# Arduino.net
KiCad netlist of a schematic drawn in EAGLE
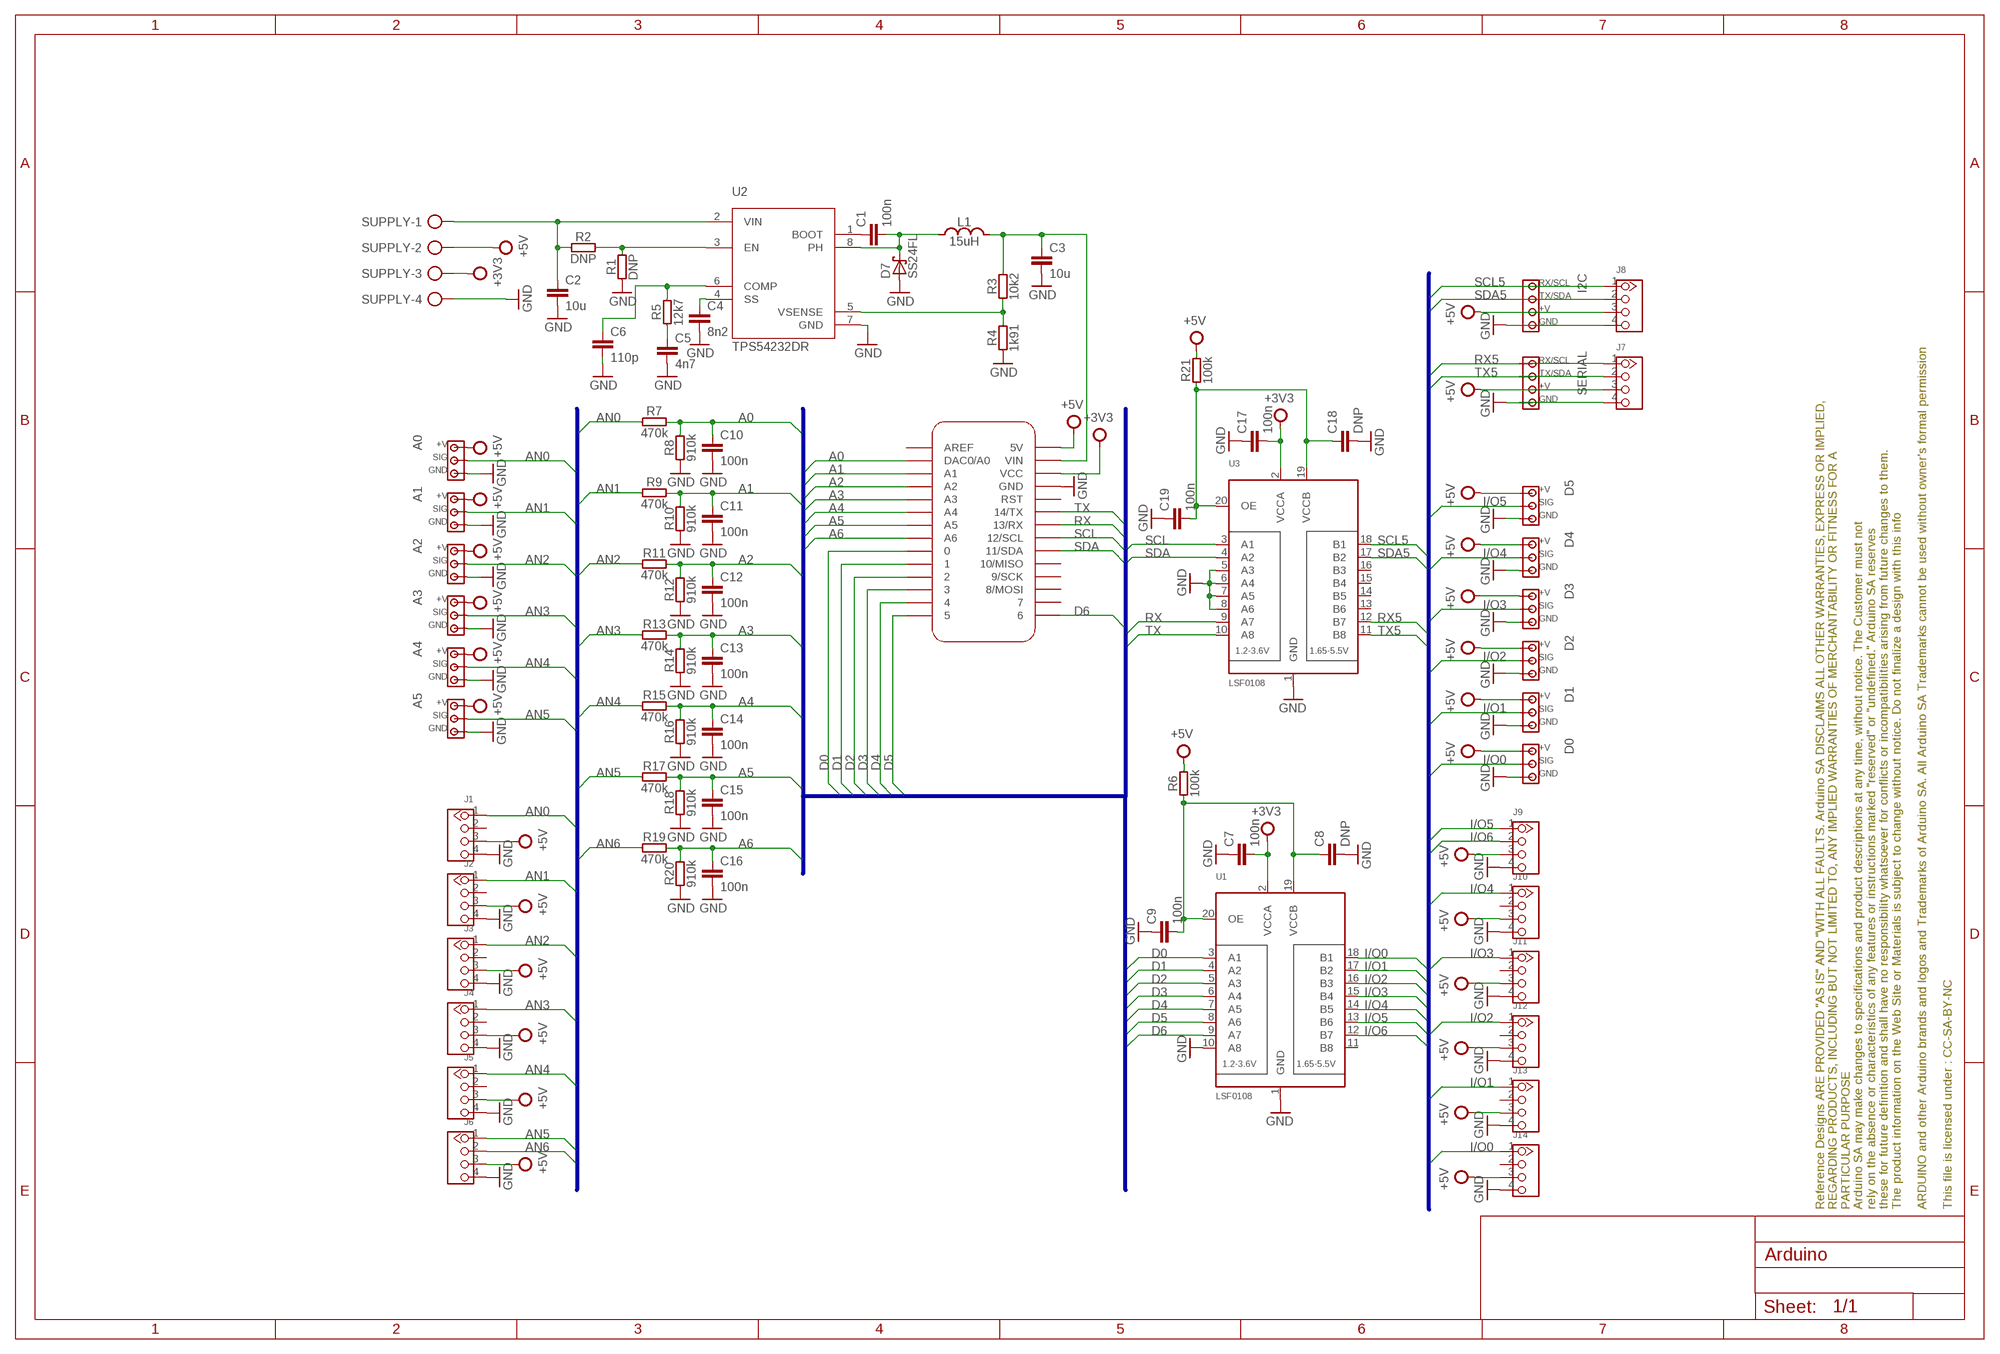
[diagram p0: schematic, sheet 1]

(export (version "E")
  (design (tool "Eeschema 10.0.6"))
  (components
    (comp (ref "A0")
      (value "DNP")
      (footprint "eagle-import:MODULINO-3SM")
      (libsource (lib "eagle-import") (part "MODULINO-3SM-DNP"))
    )
    (comp (ref "A1")
      (value "DNP")
      (footprint "eagle-import:MODULINO-3SM")
      (libsource (lib "eagle-import") (part "MODULINO-3SM-DNP"))
    )
    (comp (ref "A2")
      (value "DNP")
      (footprint "eagle-import:MODULINO-3SM")
      (libsource (lib "eagle-import") (part "MODULINO-3SM-DNP"))
    )
    (comp (ref "A3")
      (value "DNP")
      (footprint "eagle-import:MODULINO-3SM")
      (libsource (lib "eagle-import") (part "MODULINO-3SM-DNP"))
    )
    (comp (ref "A4")
      (value "DNP")
      (footprint "eagle-import:MODULINO-3SM")
      (libsource (lib "eagle-import") (part "MODULINO-3SM-DNP"))
    )
    (comp (ref "A5")
      (value "DNP")
      (footprint "eagle-import:MODULINO-3SM")
      (libsource (lib "eagle-import") (part "MODULINO-3SM-DNP"))
    )
    (comp (ref "B1")
      (value "DNP")
      (footprint "eagle-import:MKRBOARD-NOOUTLINE")
      (libsource (lib "eagle-import") (part "MKRBOARDNO-OUTLINE"))
    )
    (comp (ref "C1")
      (value "100n")
      (footprint "eagle-import:0402-1005X55N")
      (fields (field (name "MANUFACTURER") "TDK"))
      (libsource (lib "eagle-import") (part "C-0402-100NF"))
    )
    (comp (ref "C2")
      (value "10u")
      (footprint "eagle-import:0603-1608X90N")
      (fields (field (name "MANUFACTURER") "Murata"))
      (libsource (lib "eagle-import") (part "C-0603-10UF"))
    )
    (comp (ref "C3")
      (value "10u")
      (footprint "eagle-import:0603-1608X90N")
      (fields (field (name "MANUFACTURER") "Murata"))
      (libsource (lib "eagle-import") (part "C-0603-10UF"))
    )
    (comp (ref "C4")
      (value "8n2")
      (footprint "eagle-import:0402-1005X55N")
      (fields (field (name "MANUFACTURER") "Yageo"))
      (libsource (lib "eagle-import") (part "C-0402-8N2"))
    )
    (comp (ref "C5")
      (value "4n7")
      (footprint "eagle-import:0402-1005X55N")
      (fields (field (name "MANUFACTURER") "Murata"))
      (libsource (lib "eagle-import") (part "C-0402-4N7"))
    )
    (comp (ref "C6")
      (value "110p")
      (footprint "eagle-import:0402-1005X55N")
      (fields (field (name "MANUFACTURER") "Murata"))
      (libsource (lib "eagle-import") (part "C-0402-110P"))
    )
    (comp (ref "C7")
      (value "100n")
      (footprint "eagle-import:0402-1005X55N")
      (fields (field (name "MANUFACTURER") "TDK"))
      (libsource (lib "eagle-import") (part "C-0402-100NF"))
    )
    (comp (ref "C8")
      (value "DNP")
      (footprint "eagle-import:0402-1005X55N")
      (libsource (lib "eagle-import") (part "C-0402DNP"))
    )
    (comp (ref "C9")
      (value "100n")
      (footprint "eagle-import:0402-1005X55N")
      (fields (field (name "MANUFACTURER") "TDK"))
      (libsource (lib "eagle-import") (part "C-0402-100NF"))
    )
    (comp (ref "C10")
      (value "100n")
      (footprint "eagle-import:0402-1005X55N")
      (fields (field (name "MANUFACTURER") "TDK"))
      (libsource (lib "eagle-import") (part "C-0402-100NF"))
    )
    (comp (ref "C11")
      (value "100n")
      (footprint "eagle-import:0402-1005X55N")
      (fields (field (name "MANUFACTURER") "TDK"))
      (libsource (lib "eagle-import") (part "C-0402-100NF"))
    )
    (comp (ref "C12")
      (value "100n")
      (footprint "eagle-import:0402-1005X55N")
      (fields (field (name "MANUFACTURER") "TDK"))
      (libsource (lib "eagle-import") (part "C-0402-100NF"))
    )
    (comp (ref "C13")
      (value "100n")
      (footprint "eagle-import:0402-1005X55N")
      (fields (field (name "MANUFACTURER") "TDK"))
      (libsource (lib "eagle-import") (part "C-0402-100NF"))
    )
    (comp (ref "C14")
      (value "100n")
      (footprint "eagle-import:0402-1005X55N")
      (fields (field (name "MANUFACTURER") "TDK"))
      (libsource (lib "eagle-import") (part "C-0402-100NF"))
    )
    (comp (ref "C15")
      (value "100n")
      (footprint "eagle-import:0402-1005X55N")
      (fields (field (name "MANUFACTURER") "TDK"))
      (libsource (lib "eagle-import") (part "C-0402-100NF"))
    )
    (comp (ref "C16")
      (value "100n")
      (footprint "eagle-import:0402-1005X55N")
      (fields (field (name "MANUFACTURER") "TDK"))
      (libsource (lib "eagle-import") (part "C-0402-100NF"))
    )
    (comp (ref "C17")
      (value "100n")
      (footprint "eagle-import:0402-1005X55N")
      (fields (field (name "MANUFACTURER") "TDK"))
      (libsource (lib "eagle-import") (part "C-0402-100NF"))
    )
    (comp (ref "C18")
      (value "DNP")
      (footprint "eagle-import:0402-1005X55N")
      (libsource (lib "eagle-import") (part "C-0402DNP"))
    )
    (comp (ref "C19")
      (value "100n")
      (footprint "eagle-import:0402-1005X55N")
      (fields (field (name "MANUFACTURER") "TDK"))
      (libsource (lib "eagle-import") (part "C-0402-100NF"))
    )
    (comp (ref "D0")
      (value "DNP")
      (footprint "eagle-import:MODULINO-3SM")
      (libsource (lib "eagle-import") (part "MODULINO-3SM-DNP"))
    )
    (comp (ref "D1")
      (value "DNP")
      (footprint "eagle-import:MODULINO-3SM")
      (libsource (lib "eagle-import") (part "MODULINO-3SM-DNP"))
    )
    (comp (ref "D2")
      (value "DNP")
      (footprint "eagle-import:MODULINO-3SM")
      (libsource (lib "eagle-import") (part "MODULINO-3SM-DNP"))
    )
    (comp (ref "D3")
      (value "DNP")
      (footprint "eagle-import:MODULINO-3SM")
      (libsource (lib "eagle-import") (part "MODULINO-3SM-DNP"))
    )
    (comp (ref "D4")
      (value "DNP")
      (footprint "eagle-import:MODULINO-3SM")
      (libsource (lib "eagle-import") (part "MODULINO-3SM-DNP"))
    )
    (comp (ref "D5")
      (value "DNP")
      (footprint "eagle-import:MODULINO-3SM")
      (libsource (lib "eagle-import") (part "MODULINO-3SM-DNP"))
    )
    (comp (ref "D7")
      (value "SS24FL")
      (footprint "eagle-import:SOD123F")
      (fields (field (name "MANUFACTURER") "Fairchild"))
      (libsource (lib "eagle-import") (part "SS24FL"))
    )
    (comp (ref "FRAME1")
      (value "DNP")
      (footprint "eagle-import:FRAME")
      (libsource (lib "eagle-import") (part "A3-FRAME-STANDARD"))
    )
    (comp (ref "I2C")
      (value "DNP")
      (footprint "eagle-import:MODULINO-4SM")
      (libsource (lib "eagle-import") (part "MODULINO-4SM-DNP"))
    )
    (comp (ref "J1")
      (value "-")
      (footprint "eagle-import:HW4-2.0")
      (fields (field (name "MANUFACTURER") "JST"))
      (libsource (lib "eagle-import") (part "GROVE-CONNECTOR"))
    )
    (comp (ref "J2")
      (value "-")
      (footprint "eagle-import:HW4-2.0")
      (fields (field (name "MANUFACTURER") "JST"))
      (libsource (lib "eagle-import") (part "GROVE-CONNECTOR"))
    )
    (comp (ref "J3")
      (value "-")
      (footprint "eagle-import:HW4-2.0")
      (fields (field (name "MANUFACTURER") "JST"))
      (libsource (lib "eagle-import") (part "GROVE-CONNECTOR"))
    )
    (comp (ref "J4")
      (value "-")
      (footprint "eagle-import:HW4-2.0")
      (fields (field (name "MANUFACTURER") "JST"))
      (libsource (lib "eagle-import") (part "GROVE-CONNECTOR"))
    )
    (comp (ref "J5")
      (value "-")
      (footprint "eagle-import:HW4-2.0")
      (fields (field (name "MANUFACTURER") "JST"))
      (libsource (lib "eagle-import") (part "GROVE-CONNECTOR"))
    )
    (comp (ref "J6")
      (value "-")
      (footprint "eagle-import:HW4-2.0")
      (fields (field (name "MANUFACTURER") "JST"))
      (libsource (lib "eagle-import") (part "GROVE-CONNECTOR"))
    )
    (comp (ref "J7")
      (value "-")
      (footprint "eagle-import:HW4-2.0")
      (fields (field (name "MANUFACTURER") "JST"))
      (libsource (lib "eagle-import") (part "GROVE-CONNECTOR"))
    )
    (comp (ref "J8")
      (value "-")
      (footprint "eagle-import:HW4-2.0")
      (fields (field (name "MANUFACTURER") "JST"))
      (libsource (lib "eagle-import") (part "GROVE-CONNECTOR"))
    )
    (comp (ref "J9")
      (value "-")
      (footprint "eagle-import:HW4-2.0")
      (fields (field (name "MANUFACTURER") "JST"))
      (libsource (lib "eagle-import") (part "GROVE-CONNECTOR"))
    )
    (comp (ref "J10")
      (value "-")
      (footprint "eagle-import:HW4-2.0")
      (fields (field (name "MANUFACTURER") "JST"))
      (libsource (lib "eagle-import") (part "GROVE-CONNECTOR"))
    )
    (comp (ref "J11")
      (value "-")
      (footprint "eagle-import:HW4-2.0")
      (fields (field (name "MANUFACTURER") "JST"))
      (libsource (lib "eagle-import") (part "GROVE-CONNECTOR"))
    )
    (comp (ref "J12")
      (value "-")
      (footprint "eagle-import:HW4-2.0")
      (fields (field (name "MANUFACTURER") "JST"))
      (libsource (lib "eagle-import") (part "GROVE-CONNECTOR"))
    )
    (comp (ref "J13")
      (value "-")
      (footprint "eagle-import:HW4-2.0")
      (fields (field (name "MANUFACTURER") "JST"))
      (libsource (lib "eagle-import") (part "GROVE-CONNECTOR"))
    )
    (comp (ref "J14")
      (value "-")
      (footprint "eagle-import:HW4-2.0")
      (fields (field (name "MANUFACTURER") "JST"))
      (libsource (lib "eagle-import") (part "GROVE-CONNECTOR"))
    )
    (comp (ref "L1")
      (value "15uH")
      (footprint "eagle-import:SRN6045")
      (fields (field (name "MANUFACTURER") "Bourns"))
      (libsource (lib "eagle-import") (part "LSRN"))
    )
    (comp (ref "R1")
      (value "DNP")
      (footprint "eagle-import:0402-1005X55N")
      (libsource (lib "eagle-import") (part "R-0402-DNP"))
    )
    (comp (ref "R2")
      (value "DNP")
      (footprint "eagle-import:0402-1005X55N")
      (libsource (lib "eagle-import") (part "R-0402-DNP"))
    )
    (comp (ref "R3")
      (value "10k2")
      (footprint "eagle-import:0402-1005X55N")
      (fields (field (name "MANUFACTURER") "Yageo"))
      (libsource (lib "eagle-import") (part "R-0402-10K2"))
    )
    (comp (ref "R4")
      (value "1k91")
      (footprint "eagle-import:0402-1005X55N")
      (fields (field (name "MANUFACTURER") "Yageo"))
      (libsource (lib "eagle-import") (part "R-0402-1K91"))
    )
    (comp (ref "R5")
      (value "12k7")
      (footprint "eagle-import:0402-1005X55N")
      (fields (field (name "MANUFACTURER") "Yageo"))
      (libsource (lib "eagle-import") (part "R-0402-12K7"))
    )
    (comp (ref "R6")
      (value "100k")
      (footprint "eagle-import:0402-1005X55N")
      (fields (field (name "MANUFACTURER") "Yageo "))
      (libsource (lib "eagle-import") (part "R-0402-100K"))
    )
    (comp (ref "R7")
      (value "470k")
      (footprint "eagle-import:0402-1005X55N")
      (fields (field (name "MANUFACTURER") "Yageo"))
      (libsource (lib "eagle-import") (part "R-0402-470K"))
    )
    (comp (ref "R8")
      (value "910k")
      (footprint "eagle-import:0402-1005X55N")
      (fields (field (name "MANUFACTURER") "Yageo"))
      (libsource (lib "eagle-import") (part "R-0402-910K"))
    )
    (comp (ref "R9")
      (value "470k")
      (footprint "eagle-import:0402-1005X55N")
      (fields (field (name "MANUFACTURER") "Yageo"))
      (libsource (lib "eagle-import") (part "R-0402-470K"))
    )
    (comp (ref "R10")
      (value "910k")
      (footprint "eagle-import:0402-1005X55N")
      (fields (field (name "MANUFACTURER") "Yageo"))
      (libsource (lib "eagle-import") (part "R-0402-910K"))
    )
    (comp (ref "R11")
      (value "470k")
      (footprint "eagle-import:0402-1005X55N")
      (fields (field (name "MANUFACTURER") "Yageo"))
      (libsource (lib "eagle-import") (part "R-0402-470K"))
    )
    (comp (ref "R12")
      (value "910k")
      (footprint "eagle-import:0402-1005X55N")
      (fields (field (name "MANUFACTURER") "Yageo"))
      (libsource (lib "eagle-import") (part "R-0402-910K"))
    )
    (comp (ref "R13")
      (value "470k")
      (footprint "eagle-import:0402-1005X55N")
      (fields (field (name "MANUFACTURER") "Yageo"))
      (libsource (lib "eagle-import") (part "R-0402-470K"))
    )
    (comp (ref "R14")
      (value "910k")
      (footprint "eagle-import:0402-1005X55N")
      (fields (field (name "MANUFACTURER") "Yageo"))
      (libsource (lib "eagle-import") (part "R-0402-910K"))
    )
    (comp (ref "R15")
      (value "470k")
      (footprint "eagle-import:0402-1005X55N")
      (fields (field (name "MANUFACTURER") "Yageo"))
      (libsource (lib "eagle-import") (part "R-0402-470K"))
    )
    (comp (ref "R16")
      (value "910k")
      (footprint "eagle-import:0402-1005X55N")
      (fields (field (name "MANUFACTURER") "Yageo"))
      (libsource (lib "eagle-import") (part "R-0402-910K"))
    )
    (comp (ref "R17")
      (value "470k")
      (footprint "eagle-import:0402-1005X55N")
      (fields (field (name "MANUFACTURER") "Yageo"))
      (libsource (lib "eagle-import") (part "R-0402-470K"))
    )
    (comp (ref "R18")
      (value "910k")
      (footprint "eagle-import:0402-1005X55N")
      (fields (field (name "MANUFACTURER") "Yageo"))
      (libsource (lib "eagle-import") (part "R-0402-910K"))
    )
    (comp (ref "R19")
      (value "470k")
      (footprint "eagle-import:0402-1005X55N")
      (fields (field (name "MANUFACTURER") "Yageo"))
      (libsource (lib "eagle-import") (part "R-0402-470K"))
    )
    (comp (ref "R20")
      (value "910k")
      (footprint "eagle-import:0402-1005X55N")
      (fields (field (name "MANUFACTURER") "Yageo"))
      (libsource (lib "eagle-import") (part "R-0402-910K"))
    )
    (comp (ref "R21")
      (value "100k")
      (footprint "eagle-import:0402-1005X55N")
      (fields (field (name "MANUFACTURER") "Yageo "))
      (libsource (lib "eagle-import") (part "R-0402-100K"))
    )
    (comp (ref "SERIAL")
      (value "DNP")
      (footprint "eagle-import:MODULINO-4SM")
      (libsource (lib "eagle-import") (part "MODULINO-4SM-DNP"))
    )
    (comp (ref "SUPPLY")
      (value "-")
      (footprint "eagle-import:AK300_4")
      (fields (field (name "MANUFACTURER") "On Shore"))
      (libsource (lib "eagle-import") (part "AK300/4"))
    )
    (comp (ref "U1")
      (value "LSF0108")
      (footprint "eagle-import:TSSOP20")
      (fields (field (name "MANUFACTURER") "Texas Instruments "))
      (libsource (lib "eagle-import") (part "LSF0108PWR"))
    )
    (comp (ref "U2")
      (value "TPS54232DR")
      (footprint "eagle-import:SO08")
      (fields (field (name "MANUFACTURER") "Texas Instruments"))
      (libsource (lib "eagle-import") (part "TPS54232"))
    )
    (comp (ref "U3")
      (value "LSF0108")
      (footprint "eagle-import:TSSOP20")
      (fields (field (name "MANUFACTURER") "Texas Instruments "))
      (libsource (lib "eagle-import") (part "LSF0108PWR"))
    )
  )
  (nets
    (net (code "1") (name "+3V3") (class "Default")
      (node (ref "B1") (pin "VCC") (pinfunction "VCC_VCC") (pintype "bidirectional"))
      (node (ref "C17") (pin "2") (pinfunction "2_2") (pintype "passive"))
      (node (ref "C7") (pin "2") (pinfunction "2_2") (pintype "passive"))
      (node (ref "SUPPLY") (pin "3") (pinfunction "KL_3") (pintype "passive"))
      (node (ref "U1") (pin "2") (pinfunction "VCCA_2") (pintype "bidirectional"))
      (node (ref "U3") (pin "2") (pinfunction "VCCA_2") (pintype "bidirectional"))
    )
    (net (code "2") (name "+5V") (class "Default")
      (node (ref "A0") (pin "1") (pinfunction "1_1") (pintype "passive"))
      (node (ref "A1") (pin "1") (pinfunction "1_1") (pintype "passive"))
      (node (ref "A2") (pin "1") (pinfunction "1_1") (pintype "passive"))
      (node (ref "A3") (pin "1") (pinfunction "1_1") (pintype "passive"))
      (node (ref "A4") (pin "1") (pinfunction "1_1") (pintype "passive"))
      (node (ref "A5") (pin "1") (pinfunction "1_1") (pintype "passive"))
      (node (ref "B1") (pin "5V") (pinfunction "5V_5V") (pintype "bidirectional"))
      (node (ref "D0") (pin "1") (pinfunction "1_1") (pintype "passive"))
      (node (ref "D1") (pin "1") (pinfunction "1_1") (pintype "passive"))
      (node (ref "D2") (pin "1") (pinfunction "1_1") (pintype "passive"))
      (node (ref "D3") (pin "1") (pinfunction "1_1") (pintype "passive"))
      (node (ref "D4") (pin "1") (pinfunction "1_1") (pintype "passive"))
      (node (ref "D5") (pin "1") (pinfunction "1_1") (pintype "passive"))
      (node (ref "I2C") (pin "3") (pinfunction "3_3") (pintype "passive"))
      (node (ref "J1") (pin "3") (pinfunction "3_3") (pintype "bidirectional"))
      (node (ref "J10") (pin "3") (pinfunction "3_3") (pintype "bidirectional"))
      (node (ref "J11") (pin "3") (pinfunction "3_3") (pintype "bidirectional"))
      (node (ref "J12") (pin "3") (pinfunction "3_3") (pintype "bidirectional"))
      (node (ref "J13") (pin "3") (pinfunction "3_3") (pintype "bidirectional"))
      (node (ref "J14") (pin "3") (pinfunction "3_3") (pintype "bidirectional"))
      (node (ref "J2") (pin "3") (pinfunction "3_3") (pintype "bidirectional"))
      (node (ref "J3") (pin "3") (pinfunction "3_3") (pintype "bidirectional"))
      (node (ref "J4") (pin "3") (pinfunction "3_3") (pintype "bidirectional"))
      (node (ref "J5") (pin "3") (pinfunction "3_3") (pintype "bidirectional"))
      (node (ref "J6") (pin "3") (pinfunction "3_3") (pintype "bidirectional"))
      (node (ref "J7") (pin "3") (pinfunction "3_3") (pintype "bidirectional"))
      (node (ref "J8") (pin "3") (pinfunction "3_3") (pintype "bidirectional"))
      (node (ref "J9") (pin "3") (pinfunction "3_3") (pintype "bidirectional"))
      (node (ref "R21") (pin "2") (pinfunction "2_2") (pintype "passive"))
      (node (ref "R6") (pin "2") (pinfunction "2_2") (pintype "passive"))
      (node (ref "SERIAL") (pin "3") (pinfunction "3_3") (pintype "passive"))
      (node (ref "SUPPLY") (pin "2") (pinfunction "KL_2") (pintype "passive"))
    )
    (net (code "3") (name "/A0") (class "Default")
      (node (ref "B1") (pin "A0") (pinfunction "DAC0/A0_A0") (pintype "bidirectional"))
      (node (ref "C10") (pin "1") (pinfunction "1_1") (pintype "passive"))
      (node (ref "R7") (pin "2") (pinfunction "2_2") (pintype "passive"))
      (node (ref "R8") (pin "2") (pinfunction "2_2") (pintype "passive"))
    )
    (net (code "4") (name "/A1") (class "Default")
      (node (ref "B1") (pin "A1") (pinfunction "A1_A1") (pintype "bidirectional"))
      (node (ref "C11") (pin "1") (pinfunction "1_1") (pintype "passive"))
      (node (ref "R10") (pin "2") (pinfunction "2_2") (pintype "passive"))
      (node (ref "R9") (pin "2") (pinfunction "2_2") (pintype "passive"))
    )
    (net (code "5") (name "/A2") (class "Default")
      (node (ref "B1") (pin "A2") (pinfunction "A2_A2") (pintype "bidirectional"))
      (node (ref "C12") (pin "1") (pinfunction "1_1") (pintype "passive"))
      (node (ref "R11") (pin "2") (pinfunction "2_2") (pintype "passive"))
      (node (ref "R12") (pin "2") (pinfunction "2_2") (pintype "passive"))
    )
    (net (code "6") (name "/A3") (class "Default")
      (node (ref "B1") (pin "A3") (pinfunction "A3_A3") (pintype "bidirectional"))
      (node (ref "C13") (pin "1") (pinfunction "1_1") (pintype "passive"))
      (node (ref "R13") (pin "2") (pinfunction "2_2") (pintype "passive"))
      (node (ref "R14") (pin "2") (pinfunction "2_2") (pintype "passive"))
    )
    (net (code "7") (name "/A4") (class "Default")
      (node (ref "B1") (pin "A4") (pinfunction "A4_A4") (pintype "bidirectional"))
      (node (ref "C14") (pin "1") (pinfunction "1_1") (pintype "passive"))
      (node (ref "R15") (pin "2") (pinfunction "2_2") (pintype "passive"))
      (node (ref "R16") (pin "2") (pinfunction "2_2") (pintype "passive"))
    )
    (net (code "8") (name "/A5") (class "Default")
      (node (ref "B1") (pin "A5") (pinfunction "A5_A5") (pintype "bidirectional"))
      (node (ref "C15") (pin "1") (pinfunction "1_1") (pintype "passive"))
      (node (ref "R17") (pin "2") (pinfunction "2_2") (pintype "passive"))
      (node (ref "R18") (pin "2") (pinfunction "2_2") (pintype "passive"))
    )
    (net (code "9") (name "/A6") (class "Default")
      (node (ref "B1") (pin "A6") (pinfunction "A6_A6") (pintype "bidirectional"))
      (node (ref "C16") (pin "1") (pinfunction "1_1") (pintype "passive"))
      (node (ref "R19") (pin "2") (pinfunction "2_2") (pintype "passive"))
      (node (ref "R20") (pin "2") (pinfunction "2_2") (pintype "passive"))
    )
    (net (code "10") (name "/AN0") (class "Default")
      (node (ref "A0") (pin "2") (pinfunction "2_2") (pintype "passive"))
      (node (ref "J1") (pin "1") (pinfunction "1_1") (pintype "bidirectional"))
      (node (ref "R7") (pin "1") (pinfunction "1_1") (pintype "passive"))
    )
    (net (code "11") (name "/AN1") (class "Default")
      (node (ref "A1") (pin "2") (pinfunction "2_2") (pintype "passive"))
      (node (ref "J2") (pin "1") (pinfunction "1_1") (pintype "bidirectional"))
      (node (ref "R9") (pin "1") (pinfunction "1_1") (pintype "passive"))
    )
    (net (code "12") (name "/AN2") (class "Default")
      (node (ref "A2") (pin "2") (pinfunction "2_2") (pintype "passive"))
      (node (ref "J3") (pin "1") (pinfunction "1_1") (pintype "bidirectional"))
      (node (ref "R11") (pin "1") (pinfunction "1_1") (pintype "passive"))
    )
    (net (code "13") (name "/AN3") (class "Default")
      (node (ref "A3") (pin "2") (pinfunction "2_2") (pintype "passive"))
      (node (ref "J4") (pin "1") (pinfunction "1_1") (pintype "bidirectional"))
      (node (ref "R13") (pin "1") (pinfunction "1_1") (pintype "passive"))
    )
    (net (code "14") (name "/AN4") (class "Default")
      (node (ref "A4") (pin "2") (pinfunction "2_2") (pintype "passive"))
      (node (ref "J5") (pin "1") (pinfunction "1_1") (pintype "bidirectional"))
      (node (ref "R15") (pin "1") (pinfunction "1_1") (pintype "passive"))
    )
    (net (code "15") (name "/AN5") (class "Default")
      (node (ref "A5") (pin "2") (pinfunction "2_2") (pintype "passive"))
      (node (ref "J6") (pin "1") (pinfunction "1_1") (pintype "bidirectional"))
      (node (ref "R17") (pin "1") (pinfunction "1_1") (pintype "passive"))
    )
    (net (code "16") (name "/AN6") (class "Default")
      (node (ref "J6") (pin "2") (pinfunction "2_2") (pintype "bidirectional"))
      (node (ref "R19") (pin "1") (pinfunction "1_1") (pintype "passive"))
    )
    (net (code "17") (name "/D0") (class "Default")
      (node (ref "B1") (pin "0") (pinfunction "0_0") (pintype "bidirectional"))
      (node (ref "U1") (pin "3") (pinfunction "A1_3") (pintype "bidirectional"))
    )
    (net (code "18") (name "/D1") (class "Default")
      (node (ref "B1") (pin "1") (pinfunction "1_1") (pintype "bidirectional"))
      (node (ref "U1") (pin "4") (pinfunction "A2_4") (pintype "bidirectional"))
    )
    (net (code "19") (name "/D2") (class "Default")
      (node (ref "B1") (pin "2") (pinfunction "2_2") (pintype "bidirectional"))
      (node (ref "U1") (pin "5") (pinfunction "A3_5") (pintype "bidirectional"))
    )
    (net (code "20") (name "/D3") (class "Default")
      (node (ref "B1") (pin "3") (pinfunction "3_3") (pintype "bidirectional"))
      (node (ref "U1") (pin "6") (pinfunction "A4_6") (pintype "bidirectional"))
    )
    (net (code "21") (name "/D4") (class "Default")
      (node (ref "B1") (pin "4") (pinfunction "4_4") (pintype "bidirectional"))
      (node (ref "U1") (pin "7") (pinfunction "A5_7") (pintype "bidirectional"))
    )
    (net (code "22") (name "/D5") (class "Default")
      (node (ref "B1") (pin "5") (pinfunction "5_5") (pintype "bidirectional"))
      (node (ref "U1") (pin "8") (pinfunction "A6_8") (pintype "bidirectional"))
    )
    (net (code "23") (name "/D6") (class "Default")
      (node (ref "B1") (pin "6") (pinfunction "6_6") (pintype "bidirectional"))
      (node (ref "U1") (pin "9") (pinfunction "A7_9") (pintype "bidirectional"))
    )
    (net (code "24") (name "/I{slash}O0") (class "Default")
      (node (ref "D0") (pin "2") (pinfunction "2_2") (pintype "passive"))
      (node (ref "J14") (pin "1") (pinfunction "1_1") (pintype "bidirectional"))
      (node (ref "U1") (pin "18") (pinfunction "B1_18") (pintype "bidirectional"))
    )
    (net (code "25") (name "/I{slash}O1") (class "Default")
      (node (ref "D1") (pin "2") (pinfunction "2_2") (pintype "passive"))
      (node (ref "J13") (pin "1") (pinfunction "1_1") (pintype "bidirectional"))
      (node (ref "U1") (pin "17") (pinfunction "B2_17") (pintype "bidirectional"))
    )
    (net (code "26") (name "/I{slash}O2") (class "Default")
      (node (ref "D2") (pin "2") (pinfunction "2_2") (pintype "passive"))
      (node (ref "J12") (pin "1") (pinfunction "1_1") (pintype "bidirectional"))
      (node (ref "U1") (pin "16") (pinfunction "B3_16") (pintype "bidirectional"))
    )
    (net (code "27") (name "/I{slash}O3") (class "Default")
      (node (ref "D3") (pin "2") (pinfunction "2_2") (pintype "passive"))
      (node (ref "J11") (pin "1") (pinfunction "1_1") (pintype "bidirectional"))
      (node (ref "U1") (pin "15") (pinfunction "B4_15") (pintype "bidirectional"))
    )
    (net (code "28") (name "/I{slash}O4") (class "Default")
      (node (ref "D4") (pin "2") (pinfunction "2_2") (pintype "passive"))
      (node (ref "J10") (pin "1") (pinfunction "1_1") (pintype "bidirectional"))
      (node (ref "U1") (pin "14") (pinfunction "B5_14") (pintype "bidirectional"))
    )
    (net (code "29") (name "/I{slash}O5") (class "Default")
      (node (ref "D5") (pin "2") (pinfunction "2_2") (pintype "passive"))
      (node (ref "J9") (pin "1") (pinfunction "1_1") (pintype "bidirectional"))
      (node (ref "U1") (pin "13") (pinfunction "B6_13") (pintype "bidirectional"))
    )
    (net (code "30") (name "/I{slash}O6") (class "Default")
      (node (ref "J9") (pin "2") (pinfunction "2_2") (pintype "bidirectional"))
      (node (ref "U1") (pin "12") (pinfunction "B7_12") (pintype "bidirectional"))
    )
    (net (code "31") (name "/RX") (class "Default")
      (node (ref "B1") (pin "13") (pinfunction "13/RX_13") (pintype "bidirectional"))
      (node (ref "U3") (pin "9") (pinfunction "A7_9") (pintype "bidirectional"))
    )
    (net (code "32") (name "/RX5") (class "Default")
      (node (ref "J7") (pin "1") (pinfunction "1_1") (pintype "bidirectional"))
      (node (ref "SERIAL") (pin "1") (pinfunction "1_1") (pintype "passive"))
      (node (ref "U3") (pin "12") (pinfunction "B7_12") (pintype "bidirectional"))
    )
    (net (code "33") (name "/SCL") (class "Default")
      (node (ref "B1") (pin "12") (pinfunction "12/SCL_12") (pintype "bidirectional"))
      (node (ref "U3") (pin "3") (pinfunction "A1_3") (pintype "bidirectional"))
    )
    (net (code "34") (name "/SCL5") (class "Default")
      (node (ref "I2C") (pin "1") (pinfunction "1_1") (pintype "passive"))
      (node (ref "J8") (pin "1") (pinfunction "1_1") (pintype "bidirectional"))
      (node (ref "U3") (pin "18") (pinfunction "B1_18") (pintype "bidirectional"))
    )
    (net (code "35") (name "/SDA") (class "Default")
      (node (ref "B1") (pin "11") (pinfunction "11/SDA_11") (pintype "bidirectional"))
      (node (ref "U3") (pin "4") (pinfunction "A2_4") (pintype "bidirectional"))
    )
    (net (code "36") (name "/SDA5") (class "Default")
      (node (ref "I2C") (pin "2") (pinfunction "2_2") (pintype "passive"))
      (node (ref "J8") (pin "2") (pinfunction "2_2") (pintype "bidirectional"))
      (node (ref "U3") (pin "17") (pinfunction "B2_17") (pintype "bidirectional"))
    )
    (net (code "37") (name "/TX") (class "Default")
      (node (ref "B1") (pin "14") (pinfunction "14/TX_14") (pintype "bidirectional"))
      (node (ref "U3") (pin "10") (pinfunction "A8_10") (pintype "bidirectional"))
    )
    (net (code "38") (name "/TX5") (class "Default")
      (node (ref "J7") (pin "2") (pinfunction "2_2") (pintype "bidirectional"))
      (node (ref "SERIAL") (pin "2") (pinfunction "2_2") (pintype "passive"))
      (node (ref "U3") (pin "11") (pinfunction "B8_11") (pintype "bidirectional"))
    )
    (net (code "39") (name "GND") (class "Default")
      (node (ref "A0") (pin "3") (pinfunction "3_3") (pintype "passive"))
      (node (ref "A1") (pin "3") (pinfunction "3_3") (pintype "passive"))
      (node (ref "A2") (pin "3") (pinfunction "3_3") (pintype "passive"))
      (node (ref "A3") (pin "3") (pinfunction "3_3") (pintype "passive"))
      (node (ref "A4") (pin "3") (pinfunction "3_3") (pintype "passive"))
      (node (ref "A5") (pin "3") (pinfunction "3_3") (pintype "passive"))
      (node (ref "B1") (pin "GND") (pinfunction "GND_GND") (pintype "bidirectional"))
      (node (ref "C10") (pin "2") (pinfunction "2_2") (pintype "passive"))
      (node (ref "C11") (pin "2") (pinfunction "2_2") (pintype "passive"))
      (node (ref "C12") (pin "2") (pinfunction "2_2") (pintype "passive"))
      (node (ref "C13") (pin "2") (pinfunction "2_2") (pintype "passive"))
      (node (ref "C14") (pin "2") (pinfunction "2_2") (pintype "passive"))
      (node (ref "C15") (pin "2") (pinfunction "2_2") (pintype "passive"))
      (node (ref "C16") (pin "2") (pinfunction "2_2") (pintype "passive"))
      (node (ref "C17") (pin "1") (pinfunction "1_1") (pintype "passive"))
      (node (ref "C18") (pin "2") (pinfunction "2_2") (pintype "passive"))
      (node (ref "C19") (pin "1") (pinfunction "1_1") (pintype "passive"))
      (node (ref "C2") (pin "2") (pinfunction "2_2") (pintype "passive"))
      (node (ref "C3") (pin "2") (pinfunction "2_2") (pintype "passive"))
      (node (ref "C4") (pin "2") (pinfunction "2_2") (pintype "passive"))
      (node (ref "C5") (pin "2") (pinfunction "2_2") (pintype "passive"))
      (node (ref "C6") (pin "2") (pinfunction "2_2") (pintype "passive"))
      (node (ref "C7") (pin "1") (pinfunction "1_1") (pintype "passive"))
      (node (ref "C8") (pin "2") (pinfunction "2_2") (pintype "passive"))
      (node (ref "C9") (pin "1") (pinfunction "1_1") (pintype "passive"))
      (node (ref "D0") (pin "3") (pinfunction "3_3") (pintype "passive"))
      (node (ref "D1") (pin "3") (pinfunction "3_3") (pintype "passive"))
      (node (ref "D2") (pin "3") (pinfunction "3_3") (pintype "passive"))
      (node (ref "D3") (pin "3") (pinfunction "3_3") (pintype "passive"))
      (node (ref "D4") (pin "3") (pinfunction "3_3") (pintype "passive"))
      (node (ref "D5") (pin "3") (pinfunction "3_3") (pintype "passive"))
      (node (ref "D7") (pin "A") (pinfunction "A_A") (pintype "passive"))
      (node (ref "I2C") (pin "4") (pinfunction "4_4") (pintype "passive"))
      (node (ref "J1") (pin "4") (pinfunction "4_4") (pintype "bidirectional"))
      (node (ref "J10") (pin "4") (pinfunction "4_4") (pintype "bidirectional"))
      (node (ref "J11") (pin "4") (pinfunction "4_4") (pintype "bidirectional"))
      (node (ref "J12") (pin "4") (pinfunction "4_4") (pintype "bidirectional"))
      (node (ref "J13") (pin "4") (pinfunction "4_4") (pintype "bidirectional"))
      (node (ref "J14") (pin "4") (pinfunction "4_4") (pintype "bidirectional"))
      (node (ref "J2") (pin "4") (pinfunction "4_4") (pintype "bidirectional"))
      (node (ref "J3") (pin "4") (pinfunction "4_4") (pintype "bidirectional"))
      (node (ref "J4") (pin "4") (pinfunction "4_4") (pintype "bidirectional"))
      (node (ref "J5") (pin "4") (pinfunction "4_4") (pintype "bidirectional"))
      (node (ref "J6") (pin "4") (pinfunction "4_4") (pintype "bidirectional"))
      (node (ref "J7") (pin "4") (pinfunction "4_4") (pintype "bidirectional"))
      (node (ref "J8") (pin "4") (pinfunction "4_4") (pintype "bidirectional"))
      (node (ref "J9") (pin "4") (pinfunction "4_4") (pintype "bidirectional"))
      (node (ref "R1") (pin "1") (pinfunction "1_1") (pintype "passive"))
      (node (ref "R10") (pin "1") (pinfunction "1_1") (pintype "passive"))
      (node (ref "R12") (pin "1") (pinfunction "1_1") (pintype "passive"))
      (node (ref "R14") (pin "1") (pinfunction "1_1") (pintype "passive"))
      (node (ref "R16") (pin "1") (pinfunction "1_1") (pintype "passive"))
      (node (ref "R18") (pin "1") (pinfunction "1_1") (pintype "passive"))
      (node (ref "R20") (pin "1") (pinfunction "1_1") (pintype "passive"))
      (node (ref "R4") (pin "1") (pinfunction "1_1") (pintype "passive"))
      (node (ref "R8") (pin "1") (pinfunction "1_1") (pintype "passive"))
      (node (ref "SERIAL") (pin "4") (pinfunction "4_4") (pintype "passive"))
      (node (ref "SUPPLY") (pin "4") (pinfunction "KL_4") (pintype "passive"))
      (node (ref "U1") (pin "1") (pinfunction "GND_1") (pintype "bidirectional"))
      (node (ref "U1") (pin "10") (pinfunction "A8_10") (pintype "bidirectional"))
      (node (ref "U2") (pin "7") (pinfunction "GND_7") (pintype "bidirectional"))
      (node (ref "U3") (pin "1") (pinfunction "GND_1") (pintype "bidirectional"))
      (node (ref "U3") (pin "5") (pinfunction "A3_5") (pintype "bidirectional"))
      (node (ref "U3") (pin "6") (pinfunction "A4_6") (pintype "bidirectional"))
      (node (ref "U3") (pin "7") (pinfunction "A5_7") (pintype "bidirectional"))
      (node (ref "U3") (pin "8") (pinfunction "A6_8") (pintype "bidirectional"))
    )
    (net (code "40") (name "Net-(B1-PadVIN)") (class "Default")
      (node (ref "B1") (pin "VIN") (pinfunction "VIN_VIN") (pintype "bidirectional"))
      (node (ref "C3") (pin "1") (pinfunction "1_1") (pintype "passive"))
      (node (ref "L1") (pin "2") (pinfunction "2_2") (pintype "passive"))
      (node (ref "R3") (pin "2") (pinfunction "2_2") (pintype "passive"))
    )
    (net (code "41") (name "Net-(C5-Pad1)") (class "Default")
      (node (ref "C5") (pin "1") (pinfunction "1_1") (pintype "passive"))
      (node (ref "R5") (pin "1") (pinfunction "1_1") (pintype "passive"))
    )
    (net (code "42") (name "Net-(SUPPLYA-KL)") (class "Default")
      (node (ref "C2") (pin "1") (pinfunction "1_1") (pintype "passive"))
      (node (ref "R2") (pin "1") (pinfunction "1_1") (pintype "passive"))
      (node (ref "SUPPLY") (pin "1") (pinfunction "KL_1") (pintype "passive"))
      (node (ref "U2") (pin "2") (pinfunction "VIN_2") (pintype "bidirectional"))
    )
    (net (code "43") (name "Net-(U1-OE)") (class "Default")
      (node (ref "C8") (pin "1") (pinfunction "1_1") (pintype "passive"))
      (node (ref "C9") (pin "2") (pinfunction "2_2") (pintype "passive"))
      (node (ref "R6") (pin "1") (pinfunction "1_1") (pintype "passive"))
      (node (ref "U1") (pin "19") (pinfunction "VCCB_19") (pintype "bidirectional"))
      (node (ref "U1") (pin "20") (pinfunction "OE_20") (pintype "bidirectional"))
    )
    (net (code "44") (name "Net-(U2-BOOT)") (class "Default")
      (node (ref "C1") (pin "1") (pinfunction "1_1") (pintype "passive"))
      (node (ref "U2") (pin "1") (pinfunction "BOOT_1") (pintype "bidirectional"))
    )
    (net (code "45") (name "Net-(U2-COMP)") (class "Default")
      (node (ref "C6") (pin "1") (pinfunction "1_1") (pintype "passive"))
      (node (ref "R5") (pin "2") (pinfunction "2_2") (pintype "passive"))
      (node (ref "U2") (pin "6") (pinfunction "COMP_6") (pintype "bidirectional"))
    )
    (net (code "46") (name "Net-(U2-EN)") (class "Default")
      (node (ref "R1") (pin "2") (pinfunction "2_2") (pintype "passive"))
      (node (ref "R2") (pin "2") (pinfunction "2_2") (pintype "passive"))
      (node (ref "U2") (pin "3") (pinfunction "EN_3") (pintype "bidirectional"))
    )
    (net (code "47") (name "Net-(U2-PH)") (class "Default")
      (node (ref "C1") (pin "2") (pinfunction "2_2") (pintype "passive"))
      (node (ref "D7") (pin "C") (pinfunction "C_C") (pintype "passive"))
      (node (ref "L1") (pin "1") (pinfunction "1_1") (pintype "passive"))
      (node (ref "U2") (pin "8") (pinfunction "PH_8") (pintype "bidirectional"))
    )
    (net (code "48") (name "Net-(U2-SS)") (class "Default")
      (node (ref "C4") (pin "1") (pinfunction "1_1") (pintype "passive"))
      (node (ref "U2") (pin "4") (pinfunction "SS_4") (pintype "bidirectional"))
    )
    (net (code "49") (name "Net-(U2-VSENSE)") (class "Default")
      (node (ref "R3") (pin "1") (pinfunction "1_1") (pintype "passive"))
      (node (ref "R4") (pin "2") (pinfunction "2_2") (pintype "passive"))
      (node (ref "U2") (pin "5") (pinfunction "VSENSE_5") (pintype "bidirectional"))
    )
    (net (code "50") (name "Net-(U3-OE)") (class "Default")
      (node (ref "C18") (pin "1") (pinfunction "1_1") (pintype "passive"))
      (node (ref "C19") (pin "2") (pinfunction "2_2") (pintype "passive"))
      (node (ref "R21") (pin "1") (pinfunction "1_1") (pintype "passive"))
      (node (ref "U3") (pin "19") (pinfunction "VCCB_19") (pintype "bidirectional"))
      (node (ref "U3") (pin "20") (pinfunction "OE_20") (pintype "bidirectional"))
    )
    (net (code "51") (name "unconnected-(B1-8{slash}MOSI-Pad8)") (class "Default")
      (node (ref "B1") (pin "8") (pinfunction "8/MOSI_8") (pintype "bidirectional"))
    )
    (net (code "52") (name "unconnected-(B1-9{slash}SCK-Pad9)") (class "Default")
      (node (ref "B1") (pin "9") (pinfunction "9/SCK_9") (pintype "bidirectional"))
    )
    (net (code "53") (name "unconnected-(B1-10{slash}MISO-Pad10)") (class "Default")
      (node (ref "B1") (pin "10") (pinfunction "10/MISO_10") (pintype "bidirectional"))
    )
    (net (code "54") (name "unconnected-(B1-Pad7)") (class "Default")
      (node (ref "B1") (pin "7") (pinfunction "7_7") (pintype "bidirectional"))
    )
    (net (code "55") (name "unconnected-(B1-PadAREF)") (class "Default")
      (node (ref "B1") (pin "AREF") (pinfunction "AREF_AREF") (pintype "bidirectional"))
    )
    (net (code "56") (name "unconnected-(B1-PadRST)") (class "Default")
      (node (ref "B1") (pin "RST") (pinfunction "RST_RST") (pintype "bidirectional"))
    )
    (net (code "57") (name "unconnected-(J1-Pad2)") (class "Default")
      (node (ref "J1") (pin "2") (pinfunction "2_2") (pintype "bidirectional"))
    )
    (net (code "58") (name "unconnected-(J2-Pad2)") (class "Default")
      (node (ref "J2") (pin "2") (pinfunction "2_2") (pintype "bidirectional"))
    )
    (net (code "59") (name "unconnected-(J3-Pad2)") (class "Default")
      (node (ref "J3") (pin "2") (pinfunction "2_2") (pintype "bidirectional"))
    )
    (net (code "60") (name "unconnected-(J4-Pad2)") (class "Default")
      (node (ref "J4") (pin "2") (pinfunction "2_2") (pintype "bidirectional"))
    )
    (net (code "61") (name "unconnected-(J5-Pad2)") (class "Default")
      (node (ref "J5") (pin "2") (pinfunction "2_2") (pintype "bidirectional"))
    )
    (net (code "62") (name "unconnected-(J10-Pad2)") (class "Default")
      (node (ref "J10") (pin "2") (pinfunction "2_2") (pintype "bidirectional"))
    )
    (net (code "63") (name "unconnected-(J11-Pad2)") (class "Default")
      (node (ref "J11") (pin "2") (pinfunction "2_2") (pintype "bidirectional"))
    )
    (net (code "64") (name "unconnected-(J12-Pad2)") (class "Default")
      (node (ref "J12") (pin "2") (pinfunction "2_2") (pintype "bidirectional"))
    )
    (net (code "65") (name "unconnected-(J13-Pad2)") (class "Default")
      (node (ref "J13") (pin "2") (pinfunction "2_2") (pintype "bidirectional"))
    )
    (net (code "66") (name "unconnected-(J14-Pad2)") (class "Default")
      (node (ref "J14") (pin "2") (pinfunction "2_2") (pintype "bidirectional"))
    )
    (net (code "67") (name "unconnected-(U1-B8-Pad11)") (class "Default")
      (node (ref "U1") (pin "11") (pinfunction "B8_11") (pintype "bidirectional"))
    )
    (net (code "68") (name "unconnected-(U3-B3-Pad16)") (class "Default")
      (node (ref "U3") (pin "16") (pinfunction "B3_16") (pintype "bidirectional"))
    )
    (net (code "69") (name "unconnected-(U3-B4-Pad15)") (class "Default")
      (node (ref "U3") (pin "15") (pinfunction "B4_15") (pintype "bidirectional"))
    )
    (net (code "70") (name "unconnected-(U3-B5-Pad14)") (class "Default")
      (node (ref "U3") (pin "14") (pinfunction "B5_14") (pintype "bidirectional"))
    )
    (net (code "71") (name "unconnected-(U3-B6-Pad13)") (class "Default")
      (node (ref "U3") (pin "13") (pinfunction "B6_13") (pintype "bidirectional"))
    )
  )
)
